# LED_individual_sign_Board_FINAL.net
KiCad netlist of a schematic drawn in EAGLE
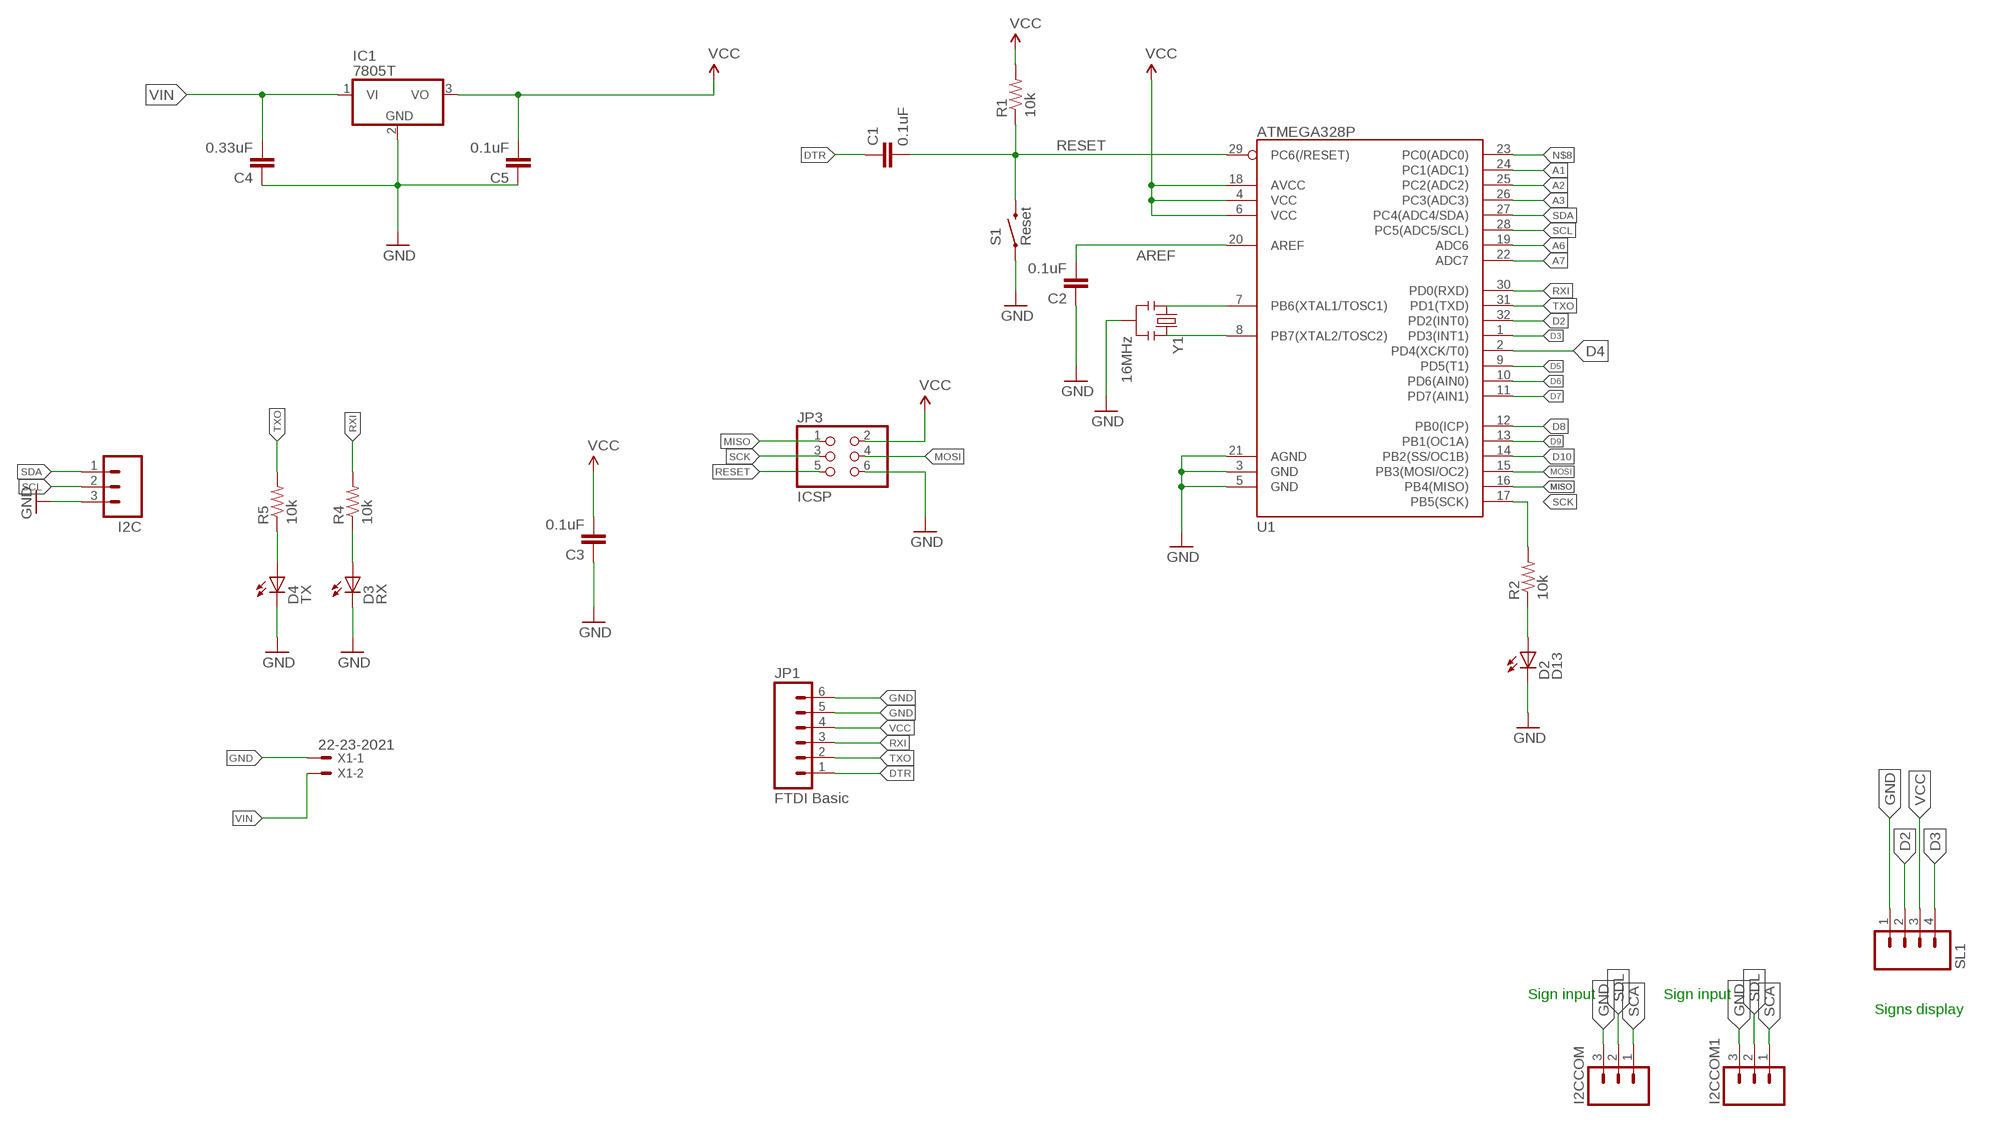
[diagram p0: schematic, sheet 1]

(export (version "E")
  (design (tool "Eeschema 10.0.6"))
  (components
    (comp (ref "C1")
      (value "0.1uF")
      (footprint "eagle-import:0603-CAP")
      (libsource (lib "eagle-import") (part "CAP0603-CAP"))
    )
    (comp (ref "C2")
      (value "0.1uF")
      (footprint "eagle-import:0603-CAP")
      (libsource (lib "eagle-import") (part "CAP0603-CAP"))
    )
    (comp (ref "C3")
      (value "0.1uF")
      (footprint "eagle-import:0603-CAP")
      (libsource (lib "eagle-import") (part "CAP0603-CAP"))
    )
    (comp (ref "C4")
      (value "0.33uF")
      (footprint "eagle-import:0603-CAP")
      (libsource (lib "eagle-import") (part "CAP0603-CAP"))
    )
    (comp (ref "C5")
      (value "0.1uF")
      (footprint "eagle-import:0603-CAP")
      (libsource (lib "eagle-import") (part "CAP0603-CAP"))
    )
    (comp (ref "D2")
      (value "D13")
      (footprint "eagle-import:LED-0603")
      (libsource (lib "eagle-import") (part "LED-RED0603"))
    )
    (comp (ref "D3")
      (value "RX")
      (footprint "eagle-import:LED-0603")
      (libsource (lib "eagle-import") (part "LED-GREEN0603"))
    )
    (comp (ref "D4")
      (value "TX")
      (footprint "eagle-import:LED-0603")
      (libsource (lib "eagle-import") (part "LED-RED0603"))
    )
    (comp (ref "I2C")
      (value "M03PTH")
      (footprint "eagle-import:1X03")
      (libsource (lib "eagle-import") (part "M03PTH"))
    )
    (comp (ref "I2CCOM")
      (value "M03PTH")
      (footprint "eagle-import:1X03")
      (libsource (lib "eagle-import") (part "M03PTH"))
    )
    (comp (ref "I2CCOM1")
      (value "M03PTH")
      (footprint "eagle-import:1X03")
      (libsource (lib "eagle-import") (part "M03PTH"))
    )
    (comp (ref "IC1")
      (value "7805T")
      (footprint "eagle-import:TO220H")
      (libsource (lib "eagle-import") (part "78T05"))
    )
    (comp (ref "JP1")
      (value "FTDI Basic")
      (footprint "eagle-import:1X06")
      (libsource (lib "eagle-import") (part "M06SIP"))
    )
    (comp (ref "JP3")
      (value "ICSP")
      (footprint "eagle-import:2X03")
      (libsource (lib "eagle-import") (part "PINHD-2X3"))
    )
    (comp (ref "R1")
      (value "10k")
      (footprint "eagle-import:0603-RES")
      (libsource (lib "eagle-import") (part "RESISTOR0603-RES"))
    )
    (comp (ref "R2")
      (value "10k")
      (footprint "eagle-import:0603-RES")
      (libsource (lib "eagle-import") (part "RESISTOR0603-RES"))
    )
    (comp (ref "R4")
      (value "10k")
      (footprint "eagle-import:0603-RES")
      (libsource (lib "eagle-import") (part "RESISTOR0603-RES"))
    )
    (comp (ref "R5")
      (value "10k")
      (footprint "eagle-import:0603-RES")
      (libsource (lib "eagle-import") (part "RESISTOR0603-RES"))
    )
    (comp (ref "S1")
      (value "Reset")
      (footprint "eagle-import:TACTILE_SWITCH_SMD")
      (libsource (lib "eagle-import") (part "SWITCH-MOMENTARY-2SMD"))
    )
    (comp (ref "SL1")
      (value "M04")
      (footprint "eagle-import:04P")
      (libsource (lib "eagle-import") (part "M04"))
    )
    (comp (ref "U1")
      (value "ATMEGA328P")
      (footprint "eagle-import:TQFP32-08")
      (libsource (lib "eagle-import") (part "ATMEGA328_SMT"))
    )
    (comp (ref "X1")
      (value "22-23-2021")
      (footprint "eagle-import:22-23-2021")
      (fields (field (name "MF") "MOLEX"))
      (libsource (lib "eagle-import") (part "22-23-2021"))
    )
    (comp (ref "Y1")
      (value "16MHz")
      (footprint "eagle-import:RESONATOR-SMD")
      (libsource (lib "eagle-import") (part "RESONATOR16MHZ"))
    )
  )
  (nets
    (net (code "1") (name "/AREF") (class "Default")
      (node (ref "C2") (pin "2") (pinfunction "2_2") (pintype "passive"))
      (node (ref "U1") (pin "20") (pinfunction "AREF_20") (pintype "bidirectional"))
    )
    (net (code "2") (name "A1") (class "Default")
      (node (ref "U1") (pin "24") (pinfunction "PC1(ADC1)_24") (pintype "bidirectional"))
    )
    (net (code "3") (name "A2") (class "Default")
      (node (ref "U1") (pin "25") (pinfunction "PC2(ADC2)_25") (pintype "bidirectional"))
    )
    (net (code "4") (name "A3") (class "Default")
      (node (ref "U1") (pin "26") (pinfunction "PC3(ADC3)_26") (pintype "bidirectional"))
    )
    (net (code "5") (name "A6") (class "Default")
      (node (ref "U1") (pin "19") (pinfunction "ADC6_19") (pintype "bidirectional"))
    )
    (net (code "6") (name "A7") (class "Default")
      (node (ref "U1") (pin "22") (pinfunction "ADC7_22") (pintype "bidirectional"))
    )
    (net (code "7") (name "D2") (class "Default")
      (node (ref "SL1") (pin "2") (pinfunction "2_2") (pintype "passive"))
      (node (ref "U1") (pin "32") (pinfunction "PD2(INT0)_32") (pintype "bidirectional"))
    )
    (net (code "8") (name "D3") (class "Default")
      (node (ref "SL1") (pin "4") (pinfunction "4_4") (pintype "passive"))
      (node (ref "U1") (pin "1") (pinfunction "PD3(INT1)_1") (pintype "bidirectional"))
    )
    (net (code "9") (name "D4") (class "Default")
      (node (ref "U1") (pin "2") (pinfunction "PD4(XCK/T0)_2") (pintype "bidirectional"))
    )
    (net (code "10") (name "D5") (class "Default")
      (node (ref "U1") (pin "9") (pinfunction "PD5(T1)_9") (pintype "bidirectional"))
    )
    (net (code "11") (name "D6") (class "Default")
      (node (ref "U1") (pin "10") (pinfunction "PD6(AIN0)_10") (pintype "bidirectional"))
    )
    (net (code "12") (name "D7") (class "Default")
      (node (ref "U1") (pin "11") (pinfunction "PD7(AIN1)_11") (pintype "bidirectional"))
    )
    (net (code "13") (name "D8") (class "Default")
      (node (ref "U1") (pin "12") (pinfunction "PB0(ICP)_12") (pintype "bidirectional"))
    )
    (net (code "14") (name "D9") (class "Default")
      (node (ref "U1") (pin "13") (pinfunction "PB1(OC1A)_13") (pintype "bidirectional"))
    )
    (net (code "15") (name "D10") (class "Default")
      (node (ref "U1") (pin "14") (pinfunction "PB2(SS/OC1B)_14") (pintype "bidirectional"))
    )
    (net (code "16") (name "DTR") (class "Default")
      (node (ref "C1") (pin "1") (pinfunction "1_1") (pintype "passive"))
      (node (ref "JP1") (pin "1") (pinfunction "1_1") (pintype "passive"))
    )
    (net (code "17") (name "GND") (class "Default")
      (node (ref "C2") (pin "1") (pinfunction "1_1") (pintype "passive"))
      (node (ref "C3") (pin "1") (pinfunction "1_1") (pintype "passive"))
      (node (ref "C4") (pin "1") (pinfunction "1_1") (pintype "passive"))
      (node (ref "C5") (pin "1") (pinfunction "1_1") (pintype "passive"))
      (node (ref "D2") (pin "C") (pinfunction "C_C") (pintype "passive"))
      (node (ref "D3") (pin "C") (pinfunction "C_C") (pintype "passive"))
      (node (ref "D4") (pin "C") (pinfunction "C_C") (pintype "passive"))
      (node (ref "I2C") (pin "3") (pinfunction "3_3") (pintype "passive"))
      (node (ref "I2CCOM") (pin "3") (pinfunction "3_3") (pintype "passive"))
      (node (ref "I2CCOM1") (pin "3") (pinfunction "3_3") (pintype "passive"))
      (node (ref "IC1") (pin "2") (pinfunction "GND_2") (pintype "passive"))
      (node (ref "JP1") (pin "5") (pinfunction "5_5") (pintype "passive"))
      (node (ref "JP1") (pin "6") (pinfunction "6_6") (pintype "passive"))
      (node (ref "JP3") (pin "6") (pinfunction "6_6") (pintype "passive"))
      (node (ref "S1") (pin "1") (pinfunction "1_1") (pintype "passive"))
      (node (ref "SL1") (pin "1") (pinfunction "1_1") (pintype "passive"))
      (node (ref "U1") (pin "21") (pinfunction "AGND_21") (pintype "bidirectional"))
      (node (ref "U1") (pin "3") (pinfunction "GND_3") (pintype "bidirectional"))
      (node (ref "U1") (pin "5") (pinfunction "GND_5") (pintype "bidirectional"))
      (node (ref "X1") (pin "1") (pinfunction "S_1") (pintype "passive"))
      (node (ref "Y1") (pin "2") (pinfunction "2_2") (pintype "passive"))
    )
    (net (code "18") (name "MISO") (class "Default")
      (node (ref "JP3") (pin "1") (pinfunction "1_1") (pintype "passive"))
      (node (ref "U1") (pin "16") (pinfunction "PB4(MISO)_16") (pintype "bidirectional"))
    )
    (net (code "19") (name "MOSI") (class "Default")
      (node (ref "JP3") (pin "4") (pinfunction "4_4") (pintype "passive"))
      (node (ref "U1") (pin "15") (pinfunction "PB3(MOSI/OC2)_15") (pintype "bidirectional"))
    )
    (net (code "20") (name "N$8") (class "Default")
      (node (ref "U1") (pin "23") (pinfunction "PC0(ADC0)_23") (pintype "bidirectional"))
    )
    (net (code "21") (name "Net-(D2-PadA)") (class "Default")
      (node (ref "D2") (pin "A") (pinfunction "A_A") (pintype "passive"))
      (node (ref "R2") (pin "1") (pinfunction "1_1") (pintype "passive"))
    )
    (net (code "22") (name "Net-(D3-PadA)") (class "Default")
      (node (ref "D3") (pin "A") (pinfunction "A_A") (pintype "passive"))
      (node (ref "R4") (pin "1") (pinfunction "1_1") (pintype "passive"))
    )
    (net (code "23") (name "Net-(D4-PadA)") (class "Default")
      (node (ref "D4") (pin "A") (pinfunction "A_A") (pintype "passive"))
      (node (ref "R5") (pin "1") (pinfunction "1_1") (pintype "passive"))
    )
    (net (code "24") (name "Net-(U1-PB6(XTAL1{slash}TOSC1))") (class "Default")
      (node (ref "U1") (pin "7") (pinfunction "PB6(XTAL1/TOSC1)_7") (pintype "bidirectional"))
      (node (ref "Y1") (pin "1") (pinfunction "1_1") (pintype "passive"))
    )
    (net (code "25") (name "Net-(U1-PB7(XTAL2{slash}TOSC2))") (class "Default")
      (node (ref "U1") (pin "8") (pinfunction "PB7(XTAL2/TOSC2)_8") (pintype "bidirectional"))
      (node (ref "Y1") (pin "3") (pinfunction "3_3") (pintype "passive"))
    )
    (net (code "26") (name "RESET") (class "Default")
      (node (ref "C1") (pin "2") (pinfunction "2_2") (pintype "passive"))
      (node (ref "JP3") (pin "5") (pinfunction "5_5") (pintype "passive"))
      (node (ref "R1") (pin "1") (pinfunction "1_1") (pintype "passive"))
      (node (ref "S1") (pin "3") (pinfunction "2_3") (pintype "passive"))
      (node (ref "U1") (pin "29") (pinfunction "PC6(/RESET)_29") (pintype "bidirectional"))
    )
    (net (code "27") (name "RXI") (class "Default")
      (node (ref "JP1") (pin "3") (pinfunction "3_3") (pintype "passive"))
      (node (ref "R4") (pin "2") (pinfunction "2_2") (pintype "passive"))
      (node (ref "U1") (pin "30") (pinfunction "PD0(RXD)_30") (pintype "bidirectional"))
    )
    (net (code "28") (name "SCA") (class "Default")
      (node (ref "I2CCOM") (pin "1") (pinfunction "1_1") (pintype "passive"))
      (node (ref "I2CCOM1") (pin "1") (pinfunction "1_1") (pintype "passive"))
    )
    (net (code "29") (name "SCK") (class "Default")
      (node (ref "JP3") (pin "3") (pinfunction "3_3") (pintype "passive"))
      (node (ref "R2") (pin "2") (pinfunction "2_2") (pintype "passive"))
      (node (ref "U1") (pin "17") (pinfunction "PB5(SCK)_17") (pintype "bidirectional"))
    )
    (net (code "30") (name "SCL") (class "Default")
      (node (ref "I2C") (pin "2") (pinfunction "2_2") (pintype "passive"))
      (node (ref "U1") (pin "28") (pinfunction "PC5(ADC5/SCL)_28") (pintype "bidirectional"))
    )
    (net (code "31") (name "SDA") (class "Default")
      (node (ref "I2C") (pin "1") (pinfunction "1_1") (pintype "passive"))
      (node (ref "U1") (pin "27") (pinfunction "PC4(ADC4/SDA)_27") (pintype "bidirectional"))
    )
    (net (code "32") (name "SDL") (class "Default")
      (node (ref "I2CCOM") (pin "2") (pinfunction "2_2") (pintype "passive"))
      (node (ref "I2CCOM1") (pin "2") (pinfunction "2_2") (pintype "passive"))
    )
    (net (code "33") (name "TXO") (class "Default")
      (node (ref "JP1") (pin "2") (pinfunction "2_2") (pintype "passive"))
      (node (ref "R5") (pin "2") (pinfunction "2_2") (pintype "passive"))
      (node (ref "U1") (pin "31") (pinfunction "PD1(TXD)_31") (pintype "bidirectional"))
    )
    (net (code "34") (name "VCC") (class "Default")
      (node (ref "C3") (pin "2") (pinfunction "2_2") (pintype "passive"))
      (node (ref "C5") (pin "2") (pinfunction "2_2") (pintype "passive"))
      (node (ref "IC1") (pin "3") (pinfunction "VO_3") (pintype "passive"))
      (node (ref "JP1") (pin "4") (pinfunction "4_4") (pintype "passive"))
      (node (ref "JP3") (pin "2") (pinfunction "2_2") (pintype "passive"))
      (node (ref "R1") (pin "2") (pinfunction "2_2") (pintype "passive"))
      (node (ref "SL1") (pin "3") (pinfunction "3_3") (pintype "passive"))
      (node (ref "U1") (pin "18") (pinfunction "AVCC_18") (pintype "bidirectional"))
      (node (ref "U1") (pin "4") (pinfunction "VCC_4") (pintype "bidirectional"))
      (node (ref "U1") (pin "6") (pinfunction "VCC_6") (pintype "bidirectional"))
    )
    (net (code "35") (name "VIN") (class "Default")
      (node (ref "C4") (pin "2") (pinfunction "2_2") (pintype "passive"))
      (node (ref "IC1") (pin "1") (pinfunction "VI_1") (pintype "input"))
      (node (ref "X1") (pin "2") (pinfunction "S_2") (pintype "passive"))
    )
  )
)
